# 3_MCU.net
KiCad netlist of a schematic drawn in Altium Designer
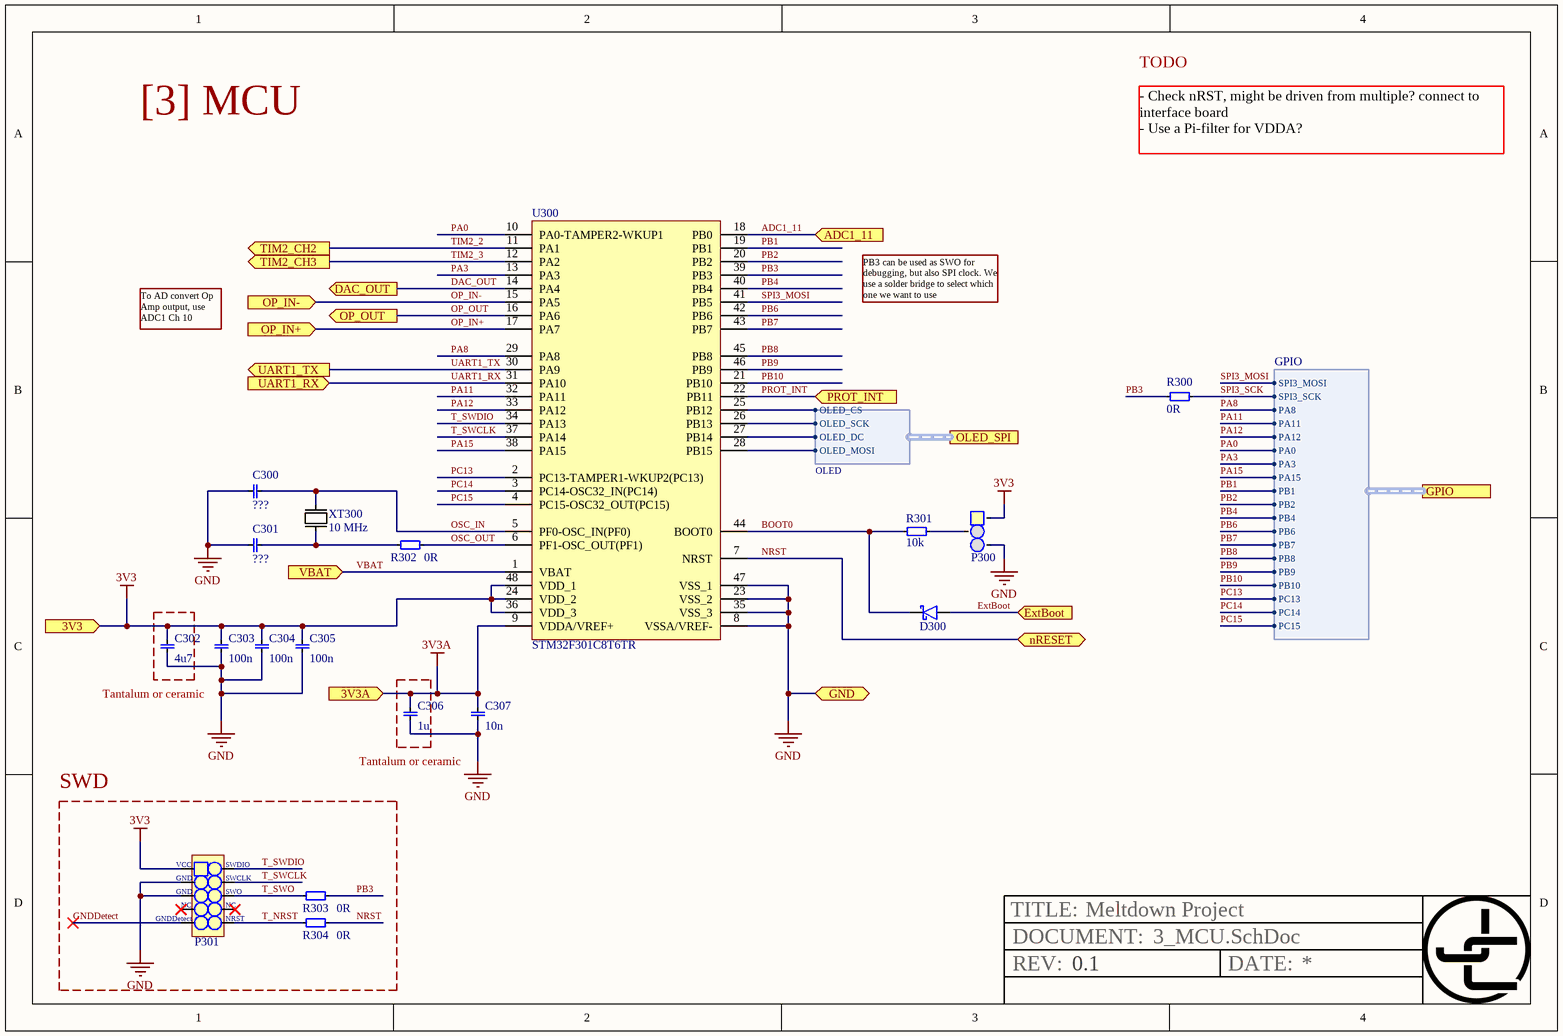
[diagram p0: 3_MCU.SchDoc]

(export (version "E")
  (design (tool "Eeschema 10.0.6"))
  (components
    (comp (ref "C300")
      (value "???")
      (footprint "0805, cap")
      (fields (field (name "Comment") "0805, capacitor"))
      (libsource (lib "jclib") (part "0805, capacitor"))
    )
    (comp (ref "C301")
      (value "???")
      (footprint "0805, cap")
      (fields (field (name "Comment") "0805, capacitor"))
      (libsource (lib "jclib") (part "0805, capacitor"))
    )
    (comp (ref "C302")
      (value "4u7")
      (footprint "0805, cap")
      (fields (field (name "Comment") "0805, capacitor"))
      (libsource (lib "jclib") (part "0805, capacitor"))
    )
    (comp (ref "C303")
      (value "100n")
      (footprint "0805, cap")
      (fields (field (name "Comment") "0805, capacitor"))
      (libsource (lib "jclib") (part "0805, capacitor"))
    )
    (comp (ref "C304")
      (value "100n")
      (footprint "0805, cap")
      (fields (field (name "Comment") "0805, capacitor"))
      (libsource (lib "jclib") (part "0805, capacitor"))
    )
    (comp (ref "C305")
      (value "100n")
      (footprint "0805, cap")
      (fields (field (name "Comment") "0805, capacitor"))
      (libsource (lib "jclib") (part "0805, capacitor"))
    )
    (comp (ref "C306")
      (value "1u")
      (footprint "0805, cap")
      (fields (field (name "Comment") "0805, capacitor"))
      (libsource (lib "jclib") (part "0805, capacitor"))
    )
    (comp (ref "C307")
      (value "10n")
      (footprint "0805, cap")
      (fields (field (name "Comment") "0805, capacitor"))
      (libsource (lib "jclib") (part "0805, capacitor"))
    )
    (comp (ref "D300")
      (value "B340A")
      (footprint "DO-214AC")
      (description "SchottkydiodE, 40 V, 3 A")
      (libsource (lib "jclib") (part "B340A-E3/61T"))
    )
    (comp (ref "P300")
      (value "1x3 Pin Header Mux")
      (footprint "padThree_L")
      (description "2.54 mm")
      (libsource (lib "jclib") (part "1x3 Pin Header Mux"))
    )
    (comp (ref "P301")
      (value "ARM 10 pin SWD")
      (footprint "FTSH-105-01-L-DV-K even odd")
      (description "1.27mm, PH")
      (libsource (lib "jclib") (part "ARM 10 pin SWD"))
    )
    (comp (ref "R300")
      (value "0R")
      (footprint "0603")
      (fields (field (name "Comment") "0603, resistor"))
      (libsource (lib "jclib") (part "0603, resistor"))
    )
    (comp (ref "R301")
      (value "10k")
      (footprint "0603")
      (fields (field (name "Comment") "0603, resistor"))
      (libsource (lib "jclib") (part "0603, resistor"))
    )
    (comp (ref "R302")
      (value "0R")
      (footprint "0603")
      (fields (field (name "Comment") "0603, resistor"))
      (libsource (lib "jclib") (part "0603, resistor"))
    )
    (comp (ref "R303")
      (value "0R")
      (footprint "0603")
      (fields (field (name "Comment") "0603, resistor"))
      (libsource (lib "jclib") (part "0603, resistor"))
    )
    (comp (ref "R304")
      (value "0R")
      (footprint "0603")
      (fields (field (name "Comment") "0603, resistor"))
      (libsource (lib "jclib") (part "0603, resistor"))
    )
    (comp (ref "U300")
      (value "STM32F301C8T6TR")
      (footprint "STM-LQFP48_L")
      (description "MCU 32-bit ARM Cortex M4 RISC 64KB Flash 2.5V/3.3V 48-Pin LQFP T/R")
      (libsource (lib "jclib") (part "STM32F301C8T6TR"))
    )
    (comp (ref "XT300")
      (value "10 MHz")
      (footprint "XTAL_SMD_LP")
      (description "10 MHz, SMD, 5mm x 3,2mm, 30 ppm")
      (fields (field (name "Comment") "XTAL ABM3"))
      (libsource (lib "jclib") (part "XTAL TXC 7A"))
    )
  )
  (nets
    (net (code "3") (name "/ADC1_11") (class "Default")
      (node (ref "U300") (pin "18") (pinfunction "PB0_18") (pintype "passive"))
    )
    (net (code "4") (name "/BOOT0") (class "Default")
      (node (ref "D300") (pin "1") (pinfunction "K_1") (pintype "passive"))
      (node (ref "R301") (pin "1") (pinfunction "1_1") (pintype "passive"))
      (node (ref "U300") (pin "44") (pinfunction "BOOT0_44") (pintype "passive"))
    )
    (net (code "5") (name "/DAC_OUT") (class "Default")
      (node (ref "U300") (pin "14") (pinfunction "PA4_14") (pintype "passive"))
    )
    (net (code "6") (name "/ExtBoot") (class "Default")
      (node (ref "D300") (pin "2") (pinfunction "A_2") (pintype "passive"))
    )
    (net (code "7") (name "/GNDDetect") (class "Default")
      (node (ref "P301") (pin "9") (pinfunction "GNDDetect_9") (pintype "passive+no_connect"))
    )
    (net (code "8") (name "/NRST") (class "Default")
      (node (ref "R304") (pin "0") (pinfunction "0_0") (pintype "passive"))
      (node (ref "U300") (pin "7") (pinfunction "NRST_7") (pintype "passive"))
    )
    (net (code "9") (name "/OLED_CS") (class "Default")
      (node (ref "U300") (pin "25") (pinfunction "PB12_25") (pintype "passive"))
    )
    (net (code "10") (name "/OLED_DC") (class "Default")
      (node (ref "U300") (pin "27") (pinfunction "PB14_27") (pintype "passive"))
    )
    (net (code "11") (name "/OLED_MOSI") (class "Default")
      (node (ref "U300") (pin "28") (pinfunction "PB15_28") (pintype "passive"))
    )
    (net (code "12") (name "/OLED_SCK") (class "Default")
      (node (ref "U300") (pin "26") (pinfunction "PB13_26") (pintype "passive"))
    )
    (net (code "13") (name "/OP_IN+") (class "Default")
      (node (ref "U300") (pin "17") (pinfunction "PA7_17") (pintype "passive"))
    )
    (net (code "14") (name "/OP_IN-") (class "Default")
      (node (ref "U300") (pin "15") (pinfunction "PA5_15") (pintype "passive"))
    )
    (net (code "15") (name "/OP_OUT") (class "Default")
      (node (ref "U300") (pin "16") (pinfunction "PA6_16") (pintype "passive"))
    )
    (net (code "16") (name "/OSC_IN") (class "Default")
      (node (ref "C300") (pin "0") (pinfunction "0_0") (pintype "passive"))
      (node (ref "U300") (pin "5") (pinfunction "PF0-OSC_IN(PF0)_5") (pintype "passive"))
      (node (ref "XT300") (pin "2") (pinfunction "2_2") (pintype "passive"))
    )
    (net (code "17") (name "/OSC_OUT") (class "Default")
      (node (ref "R302") (pin "0") (pinfunction "0_0") (pintype "passive"))
      (node (ref "U300") (pin "6") (pinfunction "PF1-OSC_OUT(PF1)_6") (pintype "passive"))
    )
    (net (code "18") (name "/PA0") (class "Default")
      (node (ref "U300") (pin "10") (pinfunction "PA0-TAMPER2-WKUP1_10") (pintype "passive"))
    )
    (net (code "19") (name "/PA3") (class "Default")
      (node (ref "U300") (pin "13") (pinfunction "PA3_13") (pintype "passive"))
    )
    (net (code "20") (name "/PA8") (class "Default")
      (node (ref "U300") (pin "29") (pinfunction "PA8_29") (pintype "passive"))
    )
    (net (code "21") (name "/PA11") (class "Default")
      (node (ref "U300") (pin "32") (pinfunction "PA11_32") (pintype "passive"))
    )
    (net (code "22") (name "/PA12") (class "Default")
      (node (ref "U300") (pin "33") (pinfunction "PA12_33") (pintype "passive"))
    )
    (net (code "23") (name "/PA15") (class "Default")
      (node (ref "U300") (pin "38") (pinfunction "PA15_38") (pintype "passive"))
    )
    (net (code "24") (name "/PB1") (class "Default")
      (node (ref "U300") (pin "19") (pinfunction "PB1_19") (pintype "passive"))
    )
    (net (code "25") (name "/PB2") (class "Default")
      (node (ref "U300") (pin "20") (pinfunction "PB2_20") (pintype "passive"))
    )
    (net (code "26") (name "/PB3") (class "Default")
      (node (ref "R300") (pin "1") (pinfunction "1_1") (pintype "passive"))
      (node (ref "R303") (pin "0") (pinfunction "0_0") (pintype "passive"))
      (node (ref "U300") (pin "39") (pinfunction "PB3_39") (pintype "passive"))
    )
    (net (code "27") (name "/PB4") (class "Default")
      (node (ref "U300") (pin "40") (pinfunction "PB4_40") (pintype "passive"))
    )
    (net (code "28") (name "/PB6") (class "Default")
      (node (ref "U300") (pin "42") (pinfunction "PB6_42") (pintype "passive"))
    )
    (net (code "29") (name "/PB7") (class "Default")
      (node (ref "U300") (pin "43") (pinfunction "PB7_43") (pintype "passive"))
    )
    (net (code "30") (name "/PB8") (class "Default")
      (node (ref "U300") (pin "45") (pinfunction "PB8_45") (pintype "passive"))
    )
    (net (code "31") (name "/PB9") (class "Default")
      (node (ref "U300") (pin "46") (pinfunction "PB9_46") (pintype "passive"))
    )
    (net (code "32") (name "/PB10") (class "Default")
      (node (ref "U300") (pin "21") (pinfunction "PB10_21") (pintype "passive"))
    )
    (net (code "33") (name "/PC13") (class "Default")
      (node (ref "U300") (pin "2") (pinfunction "PC13-TAMPER1-WKUP2(PC13)_2") (pintype "passive"))
    )
    (net (code "34") (name "/PC14") (class "Default")
      (node (ref "U300") (pin "3") (pinfunction "PC14-OSC32_IN(PC14)_3") (pintype "passive"))
    )
    (net (code "35") (name "/PC15") (class "Default")
      (node (ref "U300") (pin "4") (pinfunction "PC15-OSC32_OUT(PC15)_4") (pintype "passive"))
    )
    (net (code "36") (name "/PROT_INT") (class "Default")
      (node (ref "U300") (pin "22") (pinfunction "PB11_22") (pintype "passive"))
    )
    (net (code "37") (name "/SPI3_MOSI") (class "Default")
      (node (ref "U300") (pin "41") (pinfunction "PB5_41") (pintype "passive"))
    )
    (net (code "38") (name "/SPI3_SCK") (class "Default")
      (node (ref "R300") (pin "0") (pinfunction "0_0") (pintype "passive"))
    )
    (net (code "39") (name "/TIM2_2") (class "Default")
      (node (ref "U300") (pin "11") (pinfunction "PA1_11") (pintype "passive"))
    )
    (net (code "40") (name "/TIM2_3") (class "Default")
      (node (ref "U300") (pin "12") (pinfunction "PA2_12") (pintype "passive"))
    )
    (net (code "41") (name "/T_NRST") (class "Default")
      (node (ref "P301") (pin "10") (pinfunction "NRST_10") (pintype "passive"))
      (node (ref "R304") (pin "1") (pinfunction "1_1") (pintype "passive"))
    )
    (net (code "42") (name "/T_SWCLK") (class "Default")
      (node (ref "P301") (pin "4") (pinfunction "SWCLK_4") (pintype "passive"))
      (node (ref "U300") (pin "37") (pinfunction "PA14_37") (pintype "passive"))
    )
    (net (code "43") (name "/T_SWDIO") (class "Default")
      (node (ref "P301") (pin "2") (pinfunction "SWDIO_2") (pintype "passive"))
      (node (ref "U300") (pin "34") (pinfunction "PA13_34") (pintype "passive"))
    )
    (net (code "44") (name "/T_SWO") (class "Default")
      (node (ref "P301") (pin "6") (pinfunction "SWO_6") (pintype "passive"))
      (node (ref "R303") (pin "1") (pinfunction "1_1") (pintype "passive"))
    )
    (net (code "45") (name "/UART1_RX") (class "Default")
      (node (ref "U300") (pin "31") (pinfunction "PA10_31") (pintype "passive"))
    )
    (net (code "46") (name "/UART1_TX") (class "Default")
      (node (ref "U300") (pin "30") (pinfunction "PA9_30") (pintype "passive"))
    )
    (net (code "47") (name "/VBAT") (class "Default")
      (node (ref "U300") (pin "1") (pinfunction "VBAT_1") (pintype "passive"))
    )
    (net (code "50") (name "3V3") (class "Default")
      (node (ref "C302") (pin "1") (pinfunction "1_1") (pintype "passive"))
      (node (ref "C303") (pin "1") (pinfunction "1_1") (pintype "passive"))
      (node (ref "C304") (pin "1") (pinfunction "1_1") (pintype "passive"))
      (node (ref "C305") (pin "1") (pinfunction "1_1") (pintype "passive"))
      (node (ref "P300") (pin "1") (pinfunction "1_1") (pintype "passive"))
      (node (ref "P301") (pin "1") (pinfunction "VCC_1") (pintype "passive"))
      (node (ref "U300") (pin "24") (pinfunction "VDD_2_24") (pintype "passive"))
      (node (ref "U300") (pin "36") (pinfunction "VDD_3_36") (pintype "passive"))
      (node (ref "U300") (pin "48") (pinfunction "VDD_1_48") (pintype "passive"))
    )
    (net (code "51") (name "3V3A") (class "Default")
      (node (ref "C306") (pin "1") (pinfunction "1_1") (pintype "passive"))
      (node (ref "C307") (pin "1") (pinfunction "1_1") (pintype "passive"))
      (node (ref "U300") (pin "9") (pinfunction "VDDA/VREF+_9") (pintype "passive"))
    )
    (net (code "52") (name "GND") (class "Default")
      (node (ref "C300") (pin "1") (pinfunction "1_1") (pintype "passive"))
      (node (ref "C301") (pin "1") (pinfunction "1_1") (pintype "passive"))
      (node (ref "C302") (pin "0") (pinfunction "0_0") (pintype "passive"))
      (node (ref "C303") (pin "0") (pinfunction "0_0") (pintype "passive"))
      (node (ref "C304") (pin "0") (pinfunction "0_0") (pintype "passive"))
      (node (ref "C305") (pin "0") (pinfunction "0_0") (pintype "passive"))
      (node (ref "C306") (pin "0") (pinfunction "0_0") (pintype "passive"))
      (node (ref "C307") (pin "0") (pinfunction "0_0") (pintype "passive"))
      (node (ref "P300") (pin "3") (pinfunction "3_3") (pintype "passive"))
      (node (ref "P301") (pin "3") (pinfunction "GND_3") (pintype "passive"))
      (node (ref "P301") (pin "5") (pinfunction "GND_5") (pintype "passive"))
      (node (ref "U300") (pin "23") (pinfunction "VSS_2_23") (pintype "passive"))
      (node (ref "U300") (pin "35") (pinfunction "VSS_3_35") (pintype "passive"))
      (node (ref "U300") (pin "47") (pinfunction "VSS_1_47") (pintype "passive"))
      (node (ref "U300") (pin "8") (pinfunction "VSSA/VREF-_8") (pintype "passive"))
    )
    (net (code "53") (name "Net-(C301-Pad0)") (class "Default")
      (node (ref "C301") (pin "0") (pinfunction "0_0") (pintype "passive"))
      (node (ref "R302") (pin "1") (pinfunction "1_1") (pintype "passive"))
      (node (ref "XT300") (pin "1") (pinfunction "1_1") (pintype "passive"))
    )
    (net (code "54") (name "Net-(P300-Pad2)") (class "Default")
      (node (ref "P300") (pin "2") (pinfunction "2_2") (pintype "passive"))
      (node (ref "R301") (pin "0") (pinfunction "0_0") (pintype "passive"))
    )
    (net (code "55") (name "unconnected-(P301-NC-Pad7)") (class "Default")
      (node (ref "P301") (pin "7") (pinfunction "NC_7") (pintype "passive+no_connect"))
    )
    (net (code "56") (name "unconnected-(P301-NC-Pad8)") (class "Default")
      (node (ref "P301") (pin "8") (pinfunction "NC_8") (pintype "passive+no_connect"))
    )
  )
)
